# pc_max30003_brk.net
KiCad netlist of a schematic drawn in EAGLE
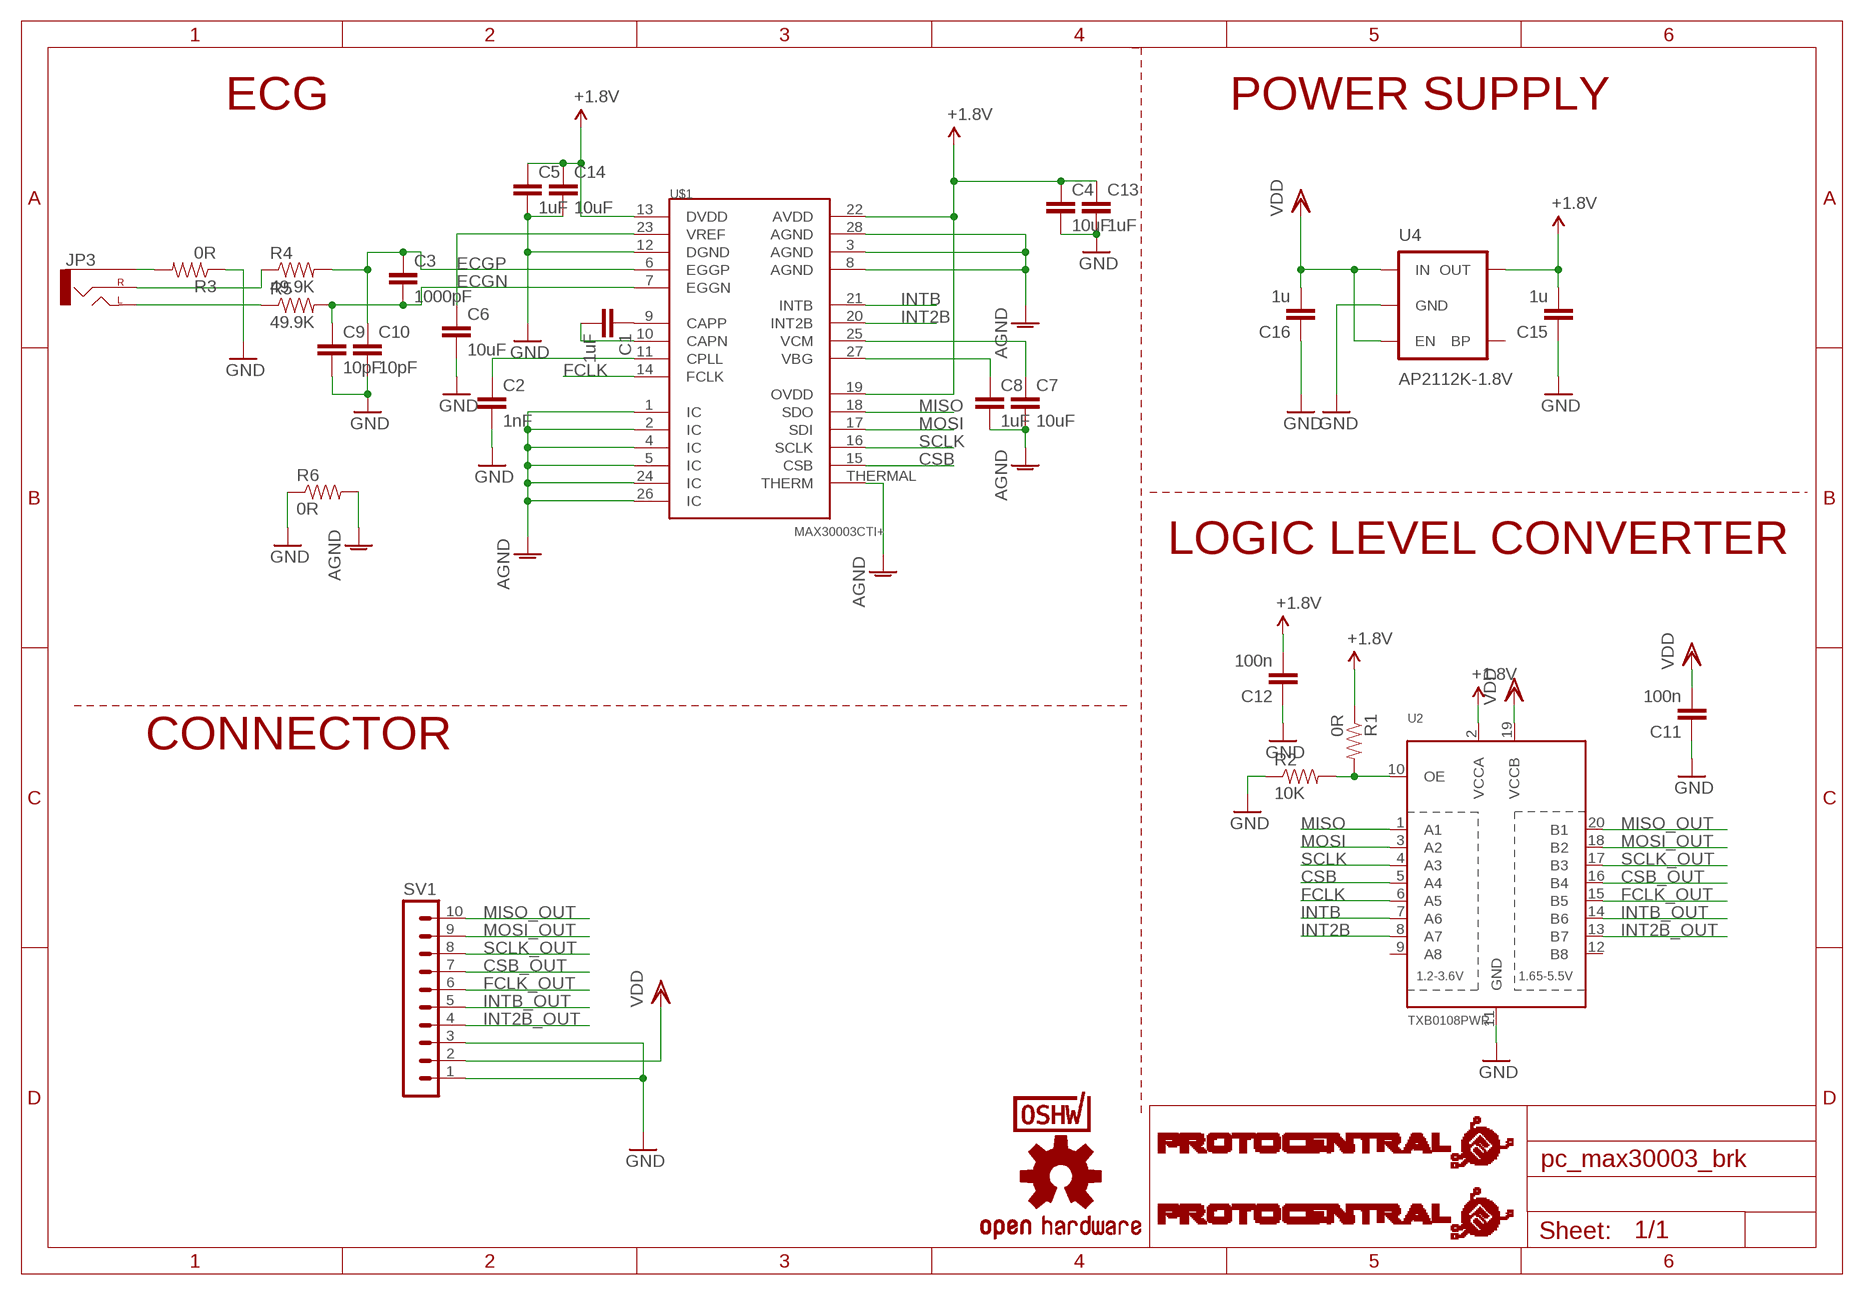
[diagram p0: schematic, sheet 1]

(export (version "E")
  (design (tool "Eeschema 10.0.6"))
  (components
    (comp (ref "C1")
      (value "1uF")
      (footprint "eagle-import:C0805")
      (libsource (lib "eagle-import") (part "C-EUC0805"))
    )
    (comp (ref "C2")
      (value "1nF")
      (footprint "eagle-import:C0805")
      (libsource (lib "eagle-import") (part "C-EUC0805"))
    )
    (comp (ref "C3")
      (value "1000pF")
      (footprint "eagle-import:C0402")
      (libsource (lib "eagle-import") (part "C-EUC0402"))
    )
    (comp (ref "C4")
      (value "10uF")
      (footprint "eagle-import:C0805")
      (libsource (lib "eagle-import") (part "C-EUC0805"))
    )
    (comp (ref "C5")
      (value "1uF")
      (footprint "eagle-import:C0805")
      (libsource (lib "eagle-import") (part "C-EUC0805"))
    )
    (comp (ref "C6")
      (value "10uF")
      (footprint "eagle-import:C0805")
      (libsource (lib "eagle-import") (part "C-EUC0805"))
    )
    (comp (ref "C7")
      (value "10uF")
      (footprint "eagle-import:C0805")
      (libsource (lib "eagle-import") (part "C-EUC0805"))
    )
    (comp (ref "C8")
      (value "1uF")
      (footprint "eagle-import:C0805")
      (libsource (lib "eagle-import") (part "C-EUC0805"))
    )
    (comp (ref "C9")
      (value "10pF")
      (footprint "eagle-import:C0402")
      (libsource (lib "eagle-import") (part "C-EUC0402"))
    )
    (comp (ref "C10")
      (value "10pF")
      (footprint "eagle-import:C0402")
      (libsource (lib "eagle-import") (part "C-EUC0402"))
    )
    (comp (ref "C11")
      (value "100n")
      (footprint "eagle-import:C0402")
      (libsource (lib "eagle-import") (part "C-EUC0402"))
    )
    (comp (ref "C12")
      (value "100n")
      (footprint "eagle-import:C0402")
      (libsource (lib "eagle-import") (part "C-EUC0402"))
    )
    (comp (ref "C13")
      (value "1uF")
      (footprint "eagle-import:C0805")
      (libsource (lib "eagle-import") (part "C-EUC0805"))
    )
    (comp (ref "C14")
      (value "10uF")
      (footprint "eagle-import:C0805")
      (libsource (lib "eagle-import") (part "C-EUC0805"))
    )
    (comp (ref "C15")
      (value "1u")
      (footprint "eagle-import:C0805")
      (libsource (lib "eagle-import") (part "C-EUC0805"))
    )
    (comp (ref "C16")
      (value "1u")
      (footprint "eagle-import:C0805")
      (libsource (lib "eagle-import") (part "C-EUC0805"))
    )
    (comp (ref "JP3")
      (value "AUDIO-JACKSMD2")
      (footprint "eagle-import:AUDIO-JACK-3.5MM-SMD")
      (libsource (lib "eagle-import") (part "AUDIO-JACKSMD2"))
    )
    (comp (ref "R1")
      (value "0R")
      (footprint "eagle-import:0805")
      (libsource (lib "eagle-import") (part "RESISTOR0805-RES"))
    )
    (comp (ref "R2")
      (value "10K")
      (footprint "eagle-import:0805")
      (libsource (lib "eagle-import") (part "RESISTOR0805-RES"))
    )
    (comp (ref "R3")
      (value "0R")
      (footprint "eagle-import:0805")
      (libsource (lib "eagle-import") (part "RESISTOR0805-RES"))
    )
    (comp (ref "R4")
      (value "49.9K")
      (footprint "eagle-import:0805")
      (libsource (lib "eagle-import") (part "RESISTOR0805-RES"))
    )
    (comp (ref "R5")
      (value "49.9K")
      (footprint "eagle-import:0805")
      (libsource (lib "eagle-import") (part "RESISTOR0805-RES"))
    )
    (comp (ref "R6")
      (value "0R")
      (footprint "eagle-import:0805")
      (libsource (lib "eagle-import") (part "RESISTOR0805-RES"))
    )
    (comp (ref "SV1")
      (value "MA10-1")
      (footprint "eagle-import:MA10-1")
      (libsource (lib "eagle-import") (part "MA10-1"))
    )
    (comp (ref "U$1")
      (value "MAX30003CTI+")
      (footprint "eagle-import:QFN-28")
      (libsource (lib "eagle-import") (part "MAX30003"))
    )
    (comp (ref "U$2")
      (value "PROTY_LOGO_WITH_TEXT")
      (footprint "eagle-import:PROTY_WITH_TEXT")
      (libsource (lib "eagle-import") (part "PROTY_LOGO_WITH_TEXT"))
    )
    (comp (ref "U$3")
      (value "PROTY-LOGO")
      (footprint "eagle-import:LOGO-PROTY")
      (libsource (lib "eagle-import") (part "PROTY-LOGO"))
    )
    (comp (ref "U$6")
      (value "OSHW-LOGOS")
      (footprint "eagle-import:OSHW-LOGO-S")
      (libsource (lib "eagle-import") (part "OSHW-LOGOS"))
    )
    (comp (ref "U$7")
      (value "CERT-SMALL")
      (footprint "eagle-import:CERT-SMALL-SILK")
      (libsource (lib "eagle-import") (part "CERT-SMALL"))
    )
    (comp (ref "U2")
      (value "TXB0108PWR")
      (footprint "eagle-import:TSSOP20")
      (libsource (lib "eagle-import") (part "TXB0108PWR"))
    )
    (comp (ref "U4")
      (value "AP2112K-1.8V")
      (footprint "eagle-import:SOT23-5")
      (libsource (lib "eagle-import") (part "V_REG_LDOSMD"))
    )
  )
  (nets
    (net (code "1") (name "+1.8V") (class "Default")
      (node (ref "C12") (pin "2") (pinfunction "2_2") (pintype "passive"))
      (node (ref "C13") (pin "1") (pinfunction "1_1") (pintype "passive"))
      (node (ref "C14") (pin "1") (pinfunction "1_1") (pintype "passive"))
      (node (ref "C15") (pin "2") (pinfunction "2_2") (pintype "passive"))
      (node (ref "C4") (pin "1") (pinfunction "1_1") (pintype "passive"))
      (node (ref "C5") (pin "1") (pinfunction "1_1") (pintype "passive"))
      (node (ref "R1") (pin "1") (pinfunction "1_1") (pintype "passive"))
      (node (ref "U$1") (pin "13") (pinfunction "DVDD_13") (pintype "bidirectional"))
      (node (ref "U$1") (pin "19") (pinfunction "OVDD_19") (pintype "bidirectional"))
      (node (ref "U$1") (pin "22") (pinfunction "AVDD_22") (pintype "bidirectional"))
      (node (ref "U2") (pin "2") (pinfunction "VCCA_2") (pintype "bidirectional"))
      (node (ref "U4") (pin "5") (pinfunction "OUT_5") (pintype "passive"))
    )
    (net (code "2") (name "/CSB") (class "Default")
      (node (ref "U$1") (pin "15") (pinfunction "CSB_15") (pintype "bidirectional"))
      (node (ref "U2") (pin "5") (pinfunction "A4_5") (pintype "bidirectional"))
    )
    (net (code "3") (name "/CSB_OUT") (class "Default")
      (node (ref "SV1") (pin "7") (pinfunction "7_7") (pintype "passive"))
      (node (ref "U2") (pin "16") (pinfunction "B4_16") (pintype "bidirectional"))
    )
    (net (code "4") (name "/ECGN") (class "Default")
      (node (ref "C3") (pin "2") (pinfunction "2_2") (pintype "passive"))
      (node (ref "C9") (pin "1") (pinfunction "1_1") (pintype "passive"))
      (node (ref "R5") (pin "2") (pinfunction "2_2") (pintype "passive"))
      (node (ref "U$1") (pin "7") (pinfunction "EGGN_7") (pintype "bidirectional"))
    )
    (net (code "5") (name "/ECGP") (class "Default")
      (node (ref "C10") (pin "1") (pinfunction "1_1") (pintype "passive"))
      (node (ref "C3") (pin "1") (pinfunction "1_1") (pintype "passive"))
      (node (ref "R4") (pin "2") (pinfunction "2_2") (pintype "passive"))
      (node (ref "U$1") (pin "6") (pinfunction "EGGP_6") (pintype "bidirectional"))
    )
    (net (code "6") (name "/FCLK") (class "Default")
      (node (ref "U$1") (pin "14") (pinfunction "FCLK_14") (pintype "bidirectional"))
      (node (ref "U2") (pin "6") (pinfunction "A5_6") (pintype "bidirectional"))
    )
    (net (code "7") (name "/FCLK_OUT") (class "Default")
      (node (ref "SV1") (pin "6") (pinfunction "6_6") (pintype "passive"))
      (node (ref "U2") (pin "15") (pinfunction "B5_15") (pintype "bidirectional"))
    )
    (net (code "8") (name "/INT2B") (class "Default")
      (node (ref "U$1") (pin "20") (pinfunction "INT2B_20") (pintype "bidirectional"))
      (node (ref "U2") (pin "8") (pinfunction "A7_8") (pintype "bidirectional"))
    )
    (net (code "9") (name "/INT2B_OUT") (class "Default")
      (node (ref "SV1") (pin "4") (pinfunction "4_4") (pintype "passive"))
      (node (ref "U2") (pin "13") (pinfunction "B7_13") (pintype "bidirectional"))
    )
    (net (code "10") (name "/INTB") (class "Default")
      (node (ref "U$1") (pin "21") (pinfunction "INTB_21") (pintype "bidirectional"))
      (node (ref "U2") (pin "7") (pinfunction "A6_7") (pintype "bidirectional"))
    )
    (net (code "11") (name "/INTB_OUT") (class "Default")
      (node (ref "SV1") (pin "5") (pinfunction "5_5") (pintype "passive"))
      (node (ref "U2") (pin "14") (pinfunction "B6_14") (pintype "bidirectional"))
    )
    (net (code "12") (name "/MISO") (class "Default")
      (node (ref "U$1") (pin "18") (pinfunction "SDO_18") (pintype "bidirectional"))
      (node (ref "U2") (pin "1") (pinfunction "A1_1") (pintype "bidirectional"))
    )
    (net (code "13") (name "/MISO_OUT") (class "Default")
      (node (ref "SV1") (pin "10") (pinfunction "10_10") (pintype "passive"))
      (node (ref "U2") (pin "20") (pinfunction "B1_20") (pintype "bidirectional"))
    )
    (net (code "14") (name "/MOSI") (class "Default")
      (node (ref "U$1") (pin "17") (pinfunction "SDI_17") (pintype "bidirectional"))
      (node (ref "U2") (pin "3") (pinfunction "A2_3") (pintype "bidirectional"))
    )
    (net (code "15") (name "/MOSI_OUT") (class "Default")
      (node (ref "SV1") (pin "9") (pinfunction "9_9") (pintype "passive"))
      (node (ref "U2") (pin "18") (pinfunction "B2_18") (pintype "bidirectional"))
    )
    (net (code "16") (name "/SCLK") (class "Default")
      (node (ref "U$1") (pin "16") (pinfunction "SCLK_16") (pintype "bidirectional"))
      (node (ref "U2") (pin "4") (pinfunction "A3_4") (pintype "bidirectional"))
    )
    (net (code "17") (name "/SCLK_OUT") (class "Default")
      (node (ref "SV1") (pin "8") (pinfunction "8_8") (pintype "passive"))
      (node (ref "U2") (pin "17") (pinfunction "B3_17") (pintype "bidirectional"))
    )
    (net (code "18") (name "AGND") (class "Default")
      (node (ref "C7") (pin "2") (pinfunction "2_2") (pintype "passive"))
      (node (ref "C8") (pin "2") (pinfunction "2_2") (pintype "passive"))
      (node (ref "R6") (pin "2") (pinfunction "2_2") (pintype "passive"))
      (node (ref "U$1") (pin "1") (pinfunction "IC_1") (pintype "bidirectional"))
      (node (ref "U$1") (pin "2") (pinfunction "IC_2") (pintype "bidirectional"))
      (node (ref "U$1") (pin "24") (pinfunction "IC_24") (pintype "bidirectional"))
      (node (ref "U$1") (pin "26") (pinfunction "IC_26") (pintype "bidirectional"))
      (node (ref "U$1") (pin "28") (pinfunction "AGND_28") (pintype "bidirectional"))
      (node (ref "U$1") (pin "3") (pinfunction "AGND_3") (pintype "bidirectional"))
      (node (ref "U$1") (pin "4") (pinfunction "IC_4") (pintype "bidirectional"))
      (node (ref "U$1") (pin "5") (pinfunction "IC_5") (pintype "bidirectional"))
      (node (ref "U$1") (pin "8") (pinfunction "AGND_8") (pintype "bidirectional"))
      (node (ref "U$1") (pin "THERMAL") (pinfunction "THERM_THERMAL") (pintype "bidirectional"))
    )
    (net (code "19") (name "GND") (class "Default")
      (node (ref "C10") (pin "2") (pinfunction "2_2") (pintype "passive"))
      (node (ref "C11") (pin "1") (pinfunction "1_1") (pintype "passive"))
      (node (ref "C12") (pin "1") (pinfunction "1_1") (pintype "passive"))
      (node (ref "C13") (pin "2") (pinfunction "2_2") (pintype "passive"))
      (node (ref "C14") (pin "2") (pinfunction "2_2") (pintype "passive"))
      (node (ref "C15") (pin "1") (pinfunction "1_1") (pintype "passive"))
      (node (ref "C16") (pin "1") (pinfunction "1_1") (pintype "passive"))
      (node (ref "C2") (pin "2") (pinfunction "2_2") (pintype "passive"))
      (node (ref "C4") (pin "2") (pinfunction "2_2") (pintype "passive"))
      (node (ref "C5") (pin "2") (pinfunction "2_2") (pintype "passive"))
      (node (ref "C6") (pin "2") (pinfunction "2_2") (pintype "passive"))
      (node (ref "C9") (pin "2") (pinfunction "2_2") (pintype "passive"))
      (node (ref "R2") (pin "1") (pinfunction "1_1") (pintype "passive"))
      (node (ref "R3") (pin "1") (pinfunction "1_1") (pintype "passive"))
      (node (ref "R6") (pin "1") (pinfunction "1_1") (pintype "passive"))
      (node (ref "SV1") (pin "1") (pinfunction "1_1") (pintype "passive"))
      (node (ref "SV1") (pin "3") (pinfunction "3_3") (pintype "passive"))
      (node (ref "U$1") (pin "12") (pinfunction "DGND_12") (pintype "bidirectional"))
      (node (ref "U2") (pin "11") (pinfunction "GND_11") (pintype "bidirectional"))
      (node (ref "U4") (pin "2") (pinfunction "GND_2") (pintype "input"))
    )
    (net (code "20") (name "Net-(JP3-LEFT)") (class "Default")
      (node (ref "JP3") (pin "TIP") (pinfunction "LEFT_TIP") (pintype "bidirectional"))
      (node (ref "R5") (pin "1") (pinfunction "1_1") (pintype "passive"))
    )
    (net (code "21") (name "Net-(JP3-PadSLEEVE)") (class "Default")
      (node (ref "JP3") (pin "SLEEVE") (pinfunction "SLEEVE_SLEEVE") (pintype "bidirectional"))
      (node (ref "R3") (pin "2") (pinfunction "2_2") (pintype "passive"))
    )
    (net (code "22") (name "Net-(JP3-RIGHT)") (class "Default")
      (node (ref "JP3") (pin "RING") (pinfunction "RIGHT_RING") (pintype "bidirectional"))
      (node (ref "R4") (pin "1") (pinfunction "1_1") (pintype "passive"))
    )
    (net (code "23") (name "Net-(U$1-CAPN)") (class "Default")
      (node (ref "C1") (pin "2") (pinfunction "2_2") (pintype "passive"))
      (node (ref "U$1") (pin "10") (pinfunction "CAPN_10") (pintype "bidirectional"))
    )
    (net (code "24") (name "Net-(U$1-CAPP)") (class "Default")
      (node (ref "C1") (pin "1") (pinfunction "1_1") (pintype "passive"))
      (node (ref "U$1") (pin "9") (pinfunction "CAPP_9") (pintype "bidirectional"))
    )
    (net (code "25") (name "Net-(U$1-CPLL)") (class "Default")
      (node (ref "C2") (pin "1") (pinfunction "1_1") (pintype "passive"))
      (node (ref "U$1") (pin "11") (pinfunction "CPLL_11") (pintype "bidirectional"))
    )
    (net (code "26") (name "Net-(U$1-VBG)") (class "Default")
      (node (ref "C8") (pin "1") (pinfunction "1_1") (pintype "passive"))
      (node (ref "U$1") (pin "27") (pinfunction "VBG_27") (pintype "bidirectional"))
    )
    (net (code "27") (name "Net-(U$1-VCM)") (class "Default")
      (node (ref "C7") (pin "1") (pinfunction "1_1") (pintype "passive"))
      (node (ref "U$1") (pin "25") (pinfunction "VCM_25") (pintype "bidirectional"))
    )
    (net (code "28") (name "Net-(U$1-VREF)") (class "Default")
      (node (ref "C6") (pin "1") (pinfunction "1_1") (pintype "passive"))
      (node (ref "U$1") (pin "23") (pinfunction "VREF_23") (pintype "bidirectional"))
    )
    (net (code "29") (name "Net-(U2-OE)") (class "Default")
      (node (ref "R1") (pin "2") (pinfunction "2_2") (pintype "passive"))
      (node (ref "R2") (pin "2") (pinfunction "2_2") (pintype "passive"))
      (node (ref "U2") (pin "10") (pinfunction "OE_10") (pintype "bidirectional"))
    )
    (net (code "30") (name "VDD") (class "Default")
      (node (ref "C11") (pin "2") (pinfunction "2_2") (pintype "passive"))
      (node (ref "C16") (pin "2") (pinfunction "2_2") (pintype "passive"))
      (node (ref "SV1") (pin "2") (pinfunction "2_2") (pintype "passive"))
      (node (ref "U2") (pin "19") (pinfunction "VCCB_19") (pintype "bidirectional"))
      (node (ref "U4") (pin "1") (pinfunction "IN_1") (pintype "input"))
      (node (ref "U4") (pin "3") (pinfunction "EN_3") (pintype "input"))
    )
    (net (code "31") (name "unconnected-(U2-A8-Pad9)") (class "Default")
      (node (ref "U2") (pin "9") (pinfunction "A8_9") (pintype "bidirectional"))
    )
    (net (code "32") (name "unconnected-(U2-B8-Pad12)") (class "Default")
      (node (ref "U2") (pin "12") (pinfunction "B8_12") (pintype "bidirectional"))
    )
    (net (code "33") (name "unconnected-(U4-BP-Pad4)") (class "Default")
      (node (ref "U4") (pin "4") (pinfunction "BP_4") (pintype "input"))
    )
  )
)
